# schaltplan_1_0.net
KiCad netlist of a schematic drawn in EAGLE
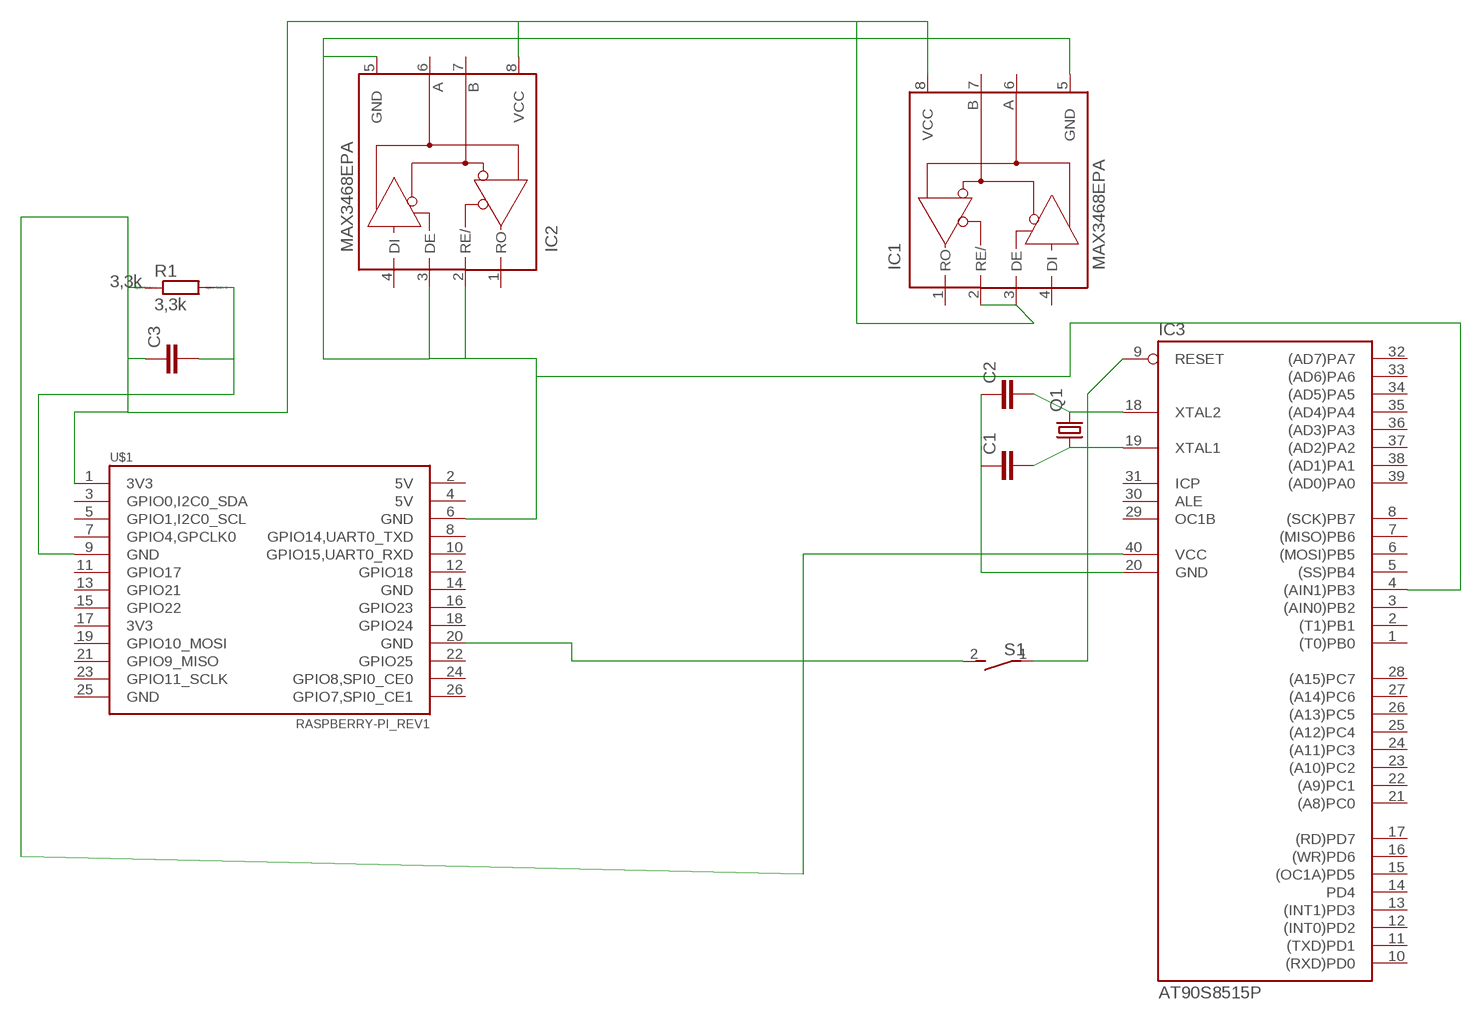
[diagram p0: schematic, sheet 1]

(export (version "E")
  (design (tool "Eeschema 10.0.6"))
  (components
    (comp (ref "C1")
      (value "C2.5/5")
      (footprint "eagle-import:C2.5-5")
      (libsource (lib "eagle-import") (part "C2.5/5"))
    )
    (comp (ref "C2")
      (value "C2.5/5")
      (footprint "eagle-import:C2.5-5")
      (libsource (lib "eagle-import") (part "C2.5/5"))
    )
    (comp (ref "C3")
      (value "C2.5/5")
      (footprint "eagle-import:C2.5-5")
      (libsource (lib "eagle-import") (part "C2.5/5"))
    )
    (comp (ref "IC1")
      (value "MAX3468EPA")
      (footprint "eagle-import:DIL08")
      (fields (field (name "MPN") "MAX3468EPA+"))
      (libsource (lib "eagle-import") (part "MAX34PA68E"))
    )
    (comp (ref "IC2")
      (value "MAX3468EPA")
      (footprint "eagle-import:DIL08")
      (fields (field (name "MPN") "MAX3468EPA+"))
      (libsource (lib "eagle-import") (part "MAX34PA68E"))
    )
    (comp (ref "IC3")
      (value "AT90S8515P")
      (footprint "eagle-import:DIL40")
      (libsource (lib "eagle-import") (part "AT90S8515P"))
    )
    (comp (ref "Q1")
      (value "CRYSTALHC49U-V")
      (footprint "eagle-import:HC49U-V")
      (libsource (lib "eagle-import") (part "CRYSTALHC49U-V"))
    )
    (comp (ref "R1")
      (value "3,3k")
      (footprint "eagle-import:0204_7")
      (fields (field (name "SPICEMODEL") "NONE") (field (name "SPICEMODEL_1") "3,3k"))
      (libsource (lib "eagle-import") (part "R0204/7"))
    )
    (comp (ref "S1")
      (value "DS01E")
      (footprint "eagle-import:DS-01")
      (libsource (lib "eagle-import") (part "DS01E"))
    )
    (comp (ref "U$1")
      (value "RASPBERRY-PI_REV1")
      (footprint "eagle-import:RASPBERRY-PI_REV1")
      (libsource (lib "eagle-import") (part "RASPBERRY-PI_REV1"))
    )
  )
  (nets
    (net (code "1") (name "Net-(C3-Pad2)") (class "Default")
      (node (ref "C3") (pin "2") (pinfunction "2_2") (pintype "passive"))
      (node (ref "R1") (pin "2") (pinfunction "2_2") (pintype "passive"))
      (node (ref "U$1") (pin "9") (pinfunction "GND_9") (pintype "bidirectional"))
    )
    (net (code "2") (name "Net-(IC1-DE)") (class "Default")
      (node (ref "C3") (pin "1") (pinfunction "1_1") (pintype "passive"))
      (node (ref "IC1") (pin "2") (pinfunction "RE/_2") (pintype "input"))
      (node (ref "IC1") (pin "3") (pinfunction "DE_3") (pintype "input"))
      (node (ref "IC1") (pin "8") (pinfunction "VCC_8") (pintype "power_in"))
      (node (ref "IC2") (pin "8") (pinfunction "VCC_8") (pintype "power_in"))
      (node (ref "IC3") (pin "40") (pinfunction "VCC_40") (pintype "power_in"))
      (node (ref "R1") (pin "1") (pinfunction "1_1") (pintype "passive"))
      (node (ref "U$1") (pin "1") (pinfunction "3V3_1") (pintype "bidirectional"))
    )
    (net (code "3") (name "Net-(IC1-GND)") (class "Default")
      (node (ref "IC1") (pin "5") (pinfunction "GND_5") (pintype "power_in"))
      (node (ref "IC2") (pin "2") (pinfunction "RE/_2") (pintype "input"))
      (node (ref "IC2") (pin "3") (pinfunction "DE_3") (pintype "input"))
      (node (ref "IC2") (pin "5") (pinfunction "GND_5") (pintype "power_in"))
      (node (ref "IC3") (pin "4") (pinfunction "(AIN1)PB3_4") (pintype "bidirectional"))
      (node (ref "U$1") (pin "6") (pinfunction "GND_6") (pintype "bidirectional"))
    )
    (net (code "4") (name "Net-(IC3-GND)") (class "Default")
      (node (ref "C1") (pin "1") (pinfunction "1_1") (pintype "passive"))
      (node (ref "C2") (pin "1") (pinfunction "1_1") (pintype "passive"))
      (node (ref "IC3") (pin "20") (pinfunction "GND_20") (pintype "power_in"))
    )
    (net (code "5") (name "Net-(IC3-RESET)") (class "Default")
      (node (ref "IC3") (pin "9") (pinfunction "RESET_9") (pintype "input"))
      (node (ref "S1") (pin "1") (pinfunction "1_1") (pintype "passive"))
    )
    (net (code "6") (name "Net-(IC3-XTAL1)") (class "Default")
      (node (ref "C1") (pin "2") (pinfunction "2_2") (pintype "passive"))
      (node (ref "IC3") (pin "19") (pinfunction "XTAL1_19") (pintype "bidirectional"))
      (node (ref "Q1") (pin "1") (pinfunction "1_1") (pintype "passive"))
    )
    (net (code "7") (name "Net-(IC3-XTAL2)") (class "Default")
      (node (ref "C2") (pin "2") (pinfunction "2_2") (pintype "passive"))
      (node (ref "IC3") (pin "18") (pinfunction "XTAL2_18") (pintype "bidirectional"))
      (node (ref "Q1") (pin "2") (pinfunction "2_2") (pintype "passive"))
    )
    (net (code "8") (name "Net-(S1-Pad2)") (class "Default")
      (node (ref "S1") (pin "2") (pinfunction "2_2") (pintype "passive"))
      (node (ref "U$1") (pin "20") (pinfunction "GND_20") (pintype "bidirectional"))
    )
    (net (code "9") (name "unconnected-(IC1-A-Pad6)") (class "Default")
      (node (ref "IC1") (pin "6") (pinfunction "A_6") (pintype "passive"))
    )
    (net (code "10") (name "unconnected-(IC1-B-Pad7)") (class "Default")
      (node (ref "IC1") (pin "7") (pinfunction "B_7") (pintype "passive"))
    )
    (net (code "11") (name "unconnected-(IC1-DI-Pad4)") (class "Default")
      (node (ref "IC1") (pin "4") (pinfunction "DI_4") (pintype "input"))
    )
    (net (code "12") (name "unconnected-(IC1-RO-Pad1)") (class "Default")
      (node (ref "IC1") (pin "1") (pinfunction "RO_1") (pintype "output"))
    )
    (net (code "13") (name "unconnected-(IC2-A-Pad6)") (class "Default")
      (node (ref "IC2") (pin "6") (pinfunction "A_6") (pintype "passive"))
    )
    (net (code "14") (name "unconnected-(IC2-B-Pad7)") (class "Default")
      (node (ref "IC2") (pin "7") (pinfunction "B_7") (pintype "passive"))
    )
    (net (code "15") (name "unconnected-(IC2-DI-Pad4)") (class "Default")
      (node (ref "IC2") (pin "4") (pinfunction "DI_4") (pintype "input"))
    )
    (net (code "16") (name "unconnected-(IC2-RO-Pad1)") (class "Default")
      (node (ref "IC2") (pin "1") (pinfunction "RO_1") (pintype "output"))
    )
    (net (code "17") (name "unconnected-(IC3-(A8)PC0-Pad21)") (class "Default")
      (node (ref "IC3") (pin "21") (pinfunction "(A8)PC0_21") (pintype "bidirectional"))
    )
    (net (code "18") (name "unconnected-(IC3-(A9)PC1-Pad22)") (class "Default")
      (node (ref "IC3") (pin "22") (pinfunction "(A9)PC1_22") (pintype "bidirectional"))
    )
    (net (code "19") (name "unconnected-(IC3-(A10)PC2-Pad23)") (class "Default")
      (node (ref "IC3") (pin "23") (pinfunction "(A10)PC2_23") (pintype "bidirectional"))
    )
    (net (code "20") (name "unconnected-(IC3-(A11)PC3-Pad24)") (class "Default")
      (node (ref "IC3") (pin "24") (pinfunction "(A11)PC3_24") (pintype "bidirectional"))
    )
    (net (code "21") (name "unconnected-(IC3-(A12)PC4-Pad25)") (class "Default")
      (node (ref "IC3") (pin "25") (pinfunction "(A12)PC4_25") (pintype "bidirectional"))
    )
    (net (code "22") (name "unconnected-(IC3-(A13)PC5-Pad26)") (class "Default")
      (node (ref "IC3") (pin "26") (pinfunction "(A13)PC5_26") (pintype "bidirectional"))
    )
    (net (code "23") (name "unconnected-(IC3-(A14)PC6-Pad27)") (class "Default")
      (node (ref "IC3") (pin "27") (pinfunction "(A14)PC6_27") (pintype "bidirectional"))
    )
    (net (code "24") (name "unconnected-(IC3-(A15)PC7-Pad28)") (class "Default")
      (node (ref "IC3") (pin "28") (pinfunction "(A15)PC7_28") (pintype "bidirectional"))
    )
    (net (code "25") (name "unconnected-(IC3-(AD0)PA0-Pad39)") (class "Default")
      (node (ref "IC3") (pin "39") (pinfunction "(AD0)PA0_39") (pintype "bidirectional"))
    )
    (net (code "26") (name "unconnected-(IC3-(AD1)PA1-Pad38)") (class "Default")
      (node (ref "IC3") (pin "38") (pinfunction "(AD1)PA1_38") (pintype "bidirectional"))
    )
    (net (code "27") (name "unconnected-(IC3-(AD2)PA2-Pad37)") (class "Default")
      (node (ref "IC3") (pin "37") (pinfunction "(AD2)PA2_37") (pintype "bidirectional"))
    )
    (net (code "28") (name "unconnected-(IC3-(AD3)PA3-Pad36)") (class "Default")
      (node (ref "IC3") (pin "36") (pinfunction "(AD3)PA3_36") (pintype "bidirectional"))
    )
    (net (code "29") (name "unconnected-(IC3-(AD4)PA4-Pad35)") (class "Default")
      (node (ref "IC3") (pin "35") (pinfunction "(AD4)PA4_35") (pintype "bidirectional"))
    )
    (net (code "30") (name "unconnected-(IC3-(AD5)PA5-Pad34)") (class "Default")
      (node (ref "IC3") (pin "34") (pinfunction "(AD5)PA5_34") (pintype "bidirectional"))
    )
    (net (code "31") (name "unconnected-(IC3-(AD6)PA6-Pad33)") (class "Default")
      (node (ref "IC3") (pin "33") (pinfunction "(AD6)PA6_33") (pintype "bidirectional"))
    )
    (net (code "32") (name "unconnected-(IC3-(AD7)PA7-Pad32)") (class "Default")
      (node (ref "IC3") (pin "32") (pinfunction "(AD7)PA7_32") (pintype "bidirectional"))
    )
    (net (code "33") (name "unconnected-(IC3-(AIN0)PB2-Pad3)") (class "Default")
      (node (ref "IC3") (pin "3") (pinfunction "(AIN0)PB2_3") (pintype "bidirectional"))
    )
    (net (code "34") (name "unconnected-(IC3-(INT0)PD2-Pad12)") (class "Default")
      (node (ref "IC3") (pin "12") (pinfunction "(INT0)PD2_12") (pintype "bidirectional"))
    )
    (net (code "35") (name "unconnected-(IC3-(INT1)PD3-Pad13)") (class "Default")
      (node (ref "IC3") (pin "13") (pinfunction "(INT1)PD3_13") (pintype "bidirectional"))
    )
    (net (code "36") (name "unconnected-(IC3-(MISO)PB6-Pad7)") (class "Default")
      (node (ref "IC3") (pin "7") (pinfunction "(MISO)PB6_7") (pintype "bidirectional"))
    )
    (net (code "37") (name "unconnected-(IC3-(MOSI)PB5-Pad6)") (class "Default")
      (node (ref "IC3") (pin "6") (pinfunction "(MOSI)PB5_6") (pintype "bidirectional"))
    )
    (net (code "38") (name "unconnected-(IC3-(OC1A)PD5-Pad15)") (class "Default")
      (node (ref "IC3") (pin "15") (pinfunction "(OC1A)PD5_15") (pintype "bidirectional"))
    )
    (net (code "39") (name "unconnected-(IC3-(RD)PD7-Pad17)") (class "Default")
      (node (ref "IC3") (pin "17") (pinfunction "(RD)PD7_17") (pintype "bidirectional"))
    )
    (net (code "40") (name "unconnected-(IC3-(RXD)PD0-Pad10)") (class "Default")
      (node (ref "IC3") (pin "10") (pinfunction "(RXD)PD0_10") (pintype "bidirectional"))
    )
    (net (code "41") (name "unconnected-(IC3-(SCK)PB7-Pad8)") (class "Default")
      (node (ref "IC3") (pin "8") (pinfunction "(SCK)PB7_8") (pintype "bidirectional"))
    )
    (net (code "42") (name "unconnected-(IC3-(SS)PB4-Pad5)") (class "Default")
      (node (ref "IC3") (pin "5") (pinfunction "(SS)PB4_5") (pintype "bidirectional"))
    )
    (net (code "43") (name "unconnected-(IC3-(T0)PB0-Pad1)") (class "Default")
      (node (ref "IC3") (pin "1") (pinfunction "(T0)PB0_1") (pintype "bidirectional"))
    )
    (net (code "44") (name "unconnected-(IC3-(T1)PB1-Pad2)") (class "Default")
      (node (ref "IC3") (pin "2") (pinfunction "(T1)PB1_2") (pintype "bidirectional"))
    )
    (net (code "45") (name "unconnected-(IC3-(TXD)PD1-Pad11)") (class "Default")
      (node (ref "IC3") (pin "11") (pinfunction "(TXD)PD1_11") (pintype "bidirectional"))
    )
    (net (code "46") (name "unconnected-(IC3-(WR)PD6-Pad16)") (class "Default")
      (node (ref "IC3") (pin "16") (pinfunction "(WR)PD6_16") (pintype "bidirectional"))
    )
    (net (code "47") (name "unconnected-(IC3-ALE-Pad30)") (class "Default")
      (node (ref "IC3") (pin "30") (pinfunction "ALE_30") (pintype "bidirectional"))
    )
    (net (code "48") (name "unconnected-(IC3-ICP-Pad31)") (class "Default")
      (node (ref "IC3") (pin "31") (pinfunction "ICP_31") (pintype "bidirectional"))
    )
    (net (code "49") (name "unconnected-(IC3-OC1B-Pad29)") (class "Default")
      (node (ref "IC3") (pin "29") (pinfunction "OC1B_29") (pintype "bidirectional"))
    )
    (net (code "50") (name "unconnected-(IC3-PD4-Pad14)") (class "Default")
      (node (ref "IC3") (pin "14") (pinfunction "PD4_14") (pintype "bidirectional"))
    )
    (net (code "51") (name "unconnected-(U$1-3V3-Pad17)") (class "Default")
      (node (ref "U$1") (pin "17") (pinfunction "3V3_17") (pintype "bidirectional"))
    )
    (net (code "52") (name "unconnected-(U$1-5V-Pad2)") (class "Default")
      (node (ref "U$1") (pin "2") (pinfunction "5V_2") (pintype "bidirectional"))
    )
    (net (code "53") (name "unconnected-(U$1-5V-Pad4)") (class "Default")
      (node (ref "U$1") (pin "4") (pinfunction "5V_4") (pintype "bidirectional"))
    )
    (net (code "54") (name "unconnected-(U$1-GND-Pad14)") (class "Default")
      (node (ref "U$1") (pin "14") (pinfunction "GND_14") (pintype "bidirectional"))
    )
    (net (code "55") (name "unconnected-(U$1-GND-Pad25)") (class "Default")
      (node (ref "U$1") (pin "25") (pinfunction "GND_25") (pintype "bidirectional"))
    )
    (net (code "56") (name "unconnected-(U$1-GPIO0,I2C0_SDA-Pad3)") (class "Default")
      (node (ref "U$1") (pin "3") (pinfunction "GPIO0,I2C0_SDA_3") (pintype "bidirectional"))
    )
    (net (code "57") (name "unconnected-(U$1-GPIO1,I2C0_SCL-Pad5)") (class "Default")
      (node (ref "U$1") (pin "5") (pinfunction "GPIO1,I2C0_SCL_5") (pintype "bidirectional"))
    )
    (net (code "58") (name "unconnected-(U$1-GPIO4,GPCLK0-Pad7)") (class "Default")
      (node (ref "U$1") (pin "7") (pinfunction "GPIO4,GPCLK0_7") (pintype "bidirectional"))
    )
    (net (code "59") (name "unconnected-(U$1-GPIO7,SPI0_CE1-Pad26)") (class "Default")
      (node (ref "U$1") (pin "26") (pinfunction "GPIO7,SPI0_CE1_26") (pintype "bidirectional"))
    )
    (net (code "60") (name "unconnected-(U$1-GPIO8,SPI0_CE0-Pad24)") (class "Default")
      (node (ref "U$1") (pin "24") (pinfunction "GPIO8,SPI0_CE0_24") (pintype "bidirectional"))
    )
    (net (code "61") (name "unconnected-(U$1-GPIO9_MISO-Pad21)") (class "Default")
      (node (ref "U$1") (pin "21") (pinfunction "GPIO9_MISO_21") (pintype "bidirectional"))
    )
    (net (code "62") (name "unconnected-(U$1-GPIO10_MOSI-Pad19)") (class "Default")
      (node (ref "U$1") (pin "19") (pinfunction "GPIO10_MOSI_19") (pintype "bidirectional"))
    )
    (net (code "63") (name "unconnected-(U$1-GPIO11_SCLK-Pad23)") (class "Default")
      (node (ref "U$1") (pin "23") (pinfunction "GPIO11_SCLK_23") (pintype "bidirectional"))
    )
    (net (code "64") (name "unconnected-(U$1-GPIO14,UART0_TXD-Pad8)") (class "Default")
      (node (ref "U$1") (pin "8") (pinfunction "GPIO14,UART0_TXD_8") (pintype "bidirectional"))
    )
    (net (code "65") (name "unconnected-(U$1-GPIO15,UART0_RXD-Pad10)") (class "Default")
      (node (ref "U$1") (pin "10") (pinfunction "GPIO15,UART0_RXD_10") (pintype "bidirectional"))
    )
    (net (code "66") (name "unconnected-(U$1-GPIO17-Pad11)") (class "Default")
      (node (ref "U$1") (pin "11") (pinfunction "GPIO17_11") (pintype "bidirectional"))
    )
    (net (code "67") (name "unconnected-(U$1-GPIO18-Pad12)") (class "Default")
      (node (ref "U$1") (pin "12") (pinfunction "GPIO18_12") (pintype "bidirectional"))
    )
    (net (code "68") (name "unconnected-(U$1-GPIO21-Pad13)") (class "Default")
      (node (ref "U$1") (pin "13") (pinfunction "GPIO21_13") (pintype "bidirectional"))
    )
    (net (code "69") (name "unconnected-(U$1-GPIO22-Pad15)") (class "Default")
      (node (ref "U$1") (pin "15") (pinfunction "GPIO22_15") (pintype "bidirectional"))
    )
    (net (code "70") (name "unconnected-(U$1-GPIO23-Pad16)") (class "Default")
      (node (ref "U$1") (pin "16") (pinfunction "GPIO23_16") (pintype "bidirectional"))
    )
    (net (code "71") (name "unconnected-(U$1-GPIO24-Pad18)") (class "Default")
      (node (ref "U$1") (pin "18") (pinfunction "GPIO24_18") (pintype "bidirectional"))
    )
    (net (code "72") (name "unconnected-(U$1-GPIO25-Pad22)") (class "Default")
      (node (ref "U$1") (pin "22") (pinfunction "GPIO25_22") (pintype "bidirectional"))
    )
  )
)
